# SCH_PET_tlacitko_V1_2023-06-28.net
KiCad netlist of a schematic drawn in EasyEDA
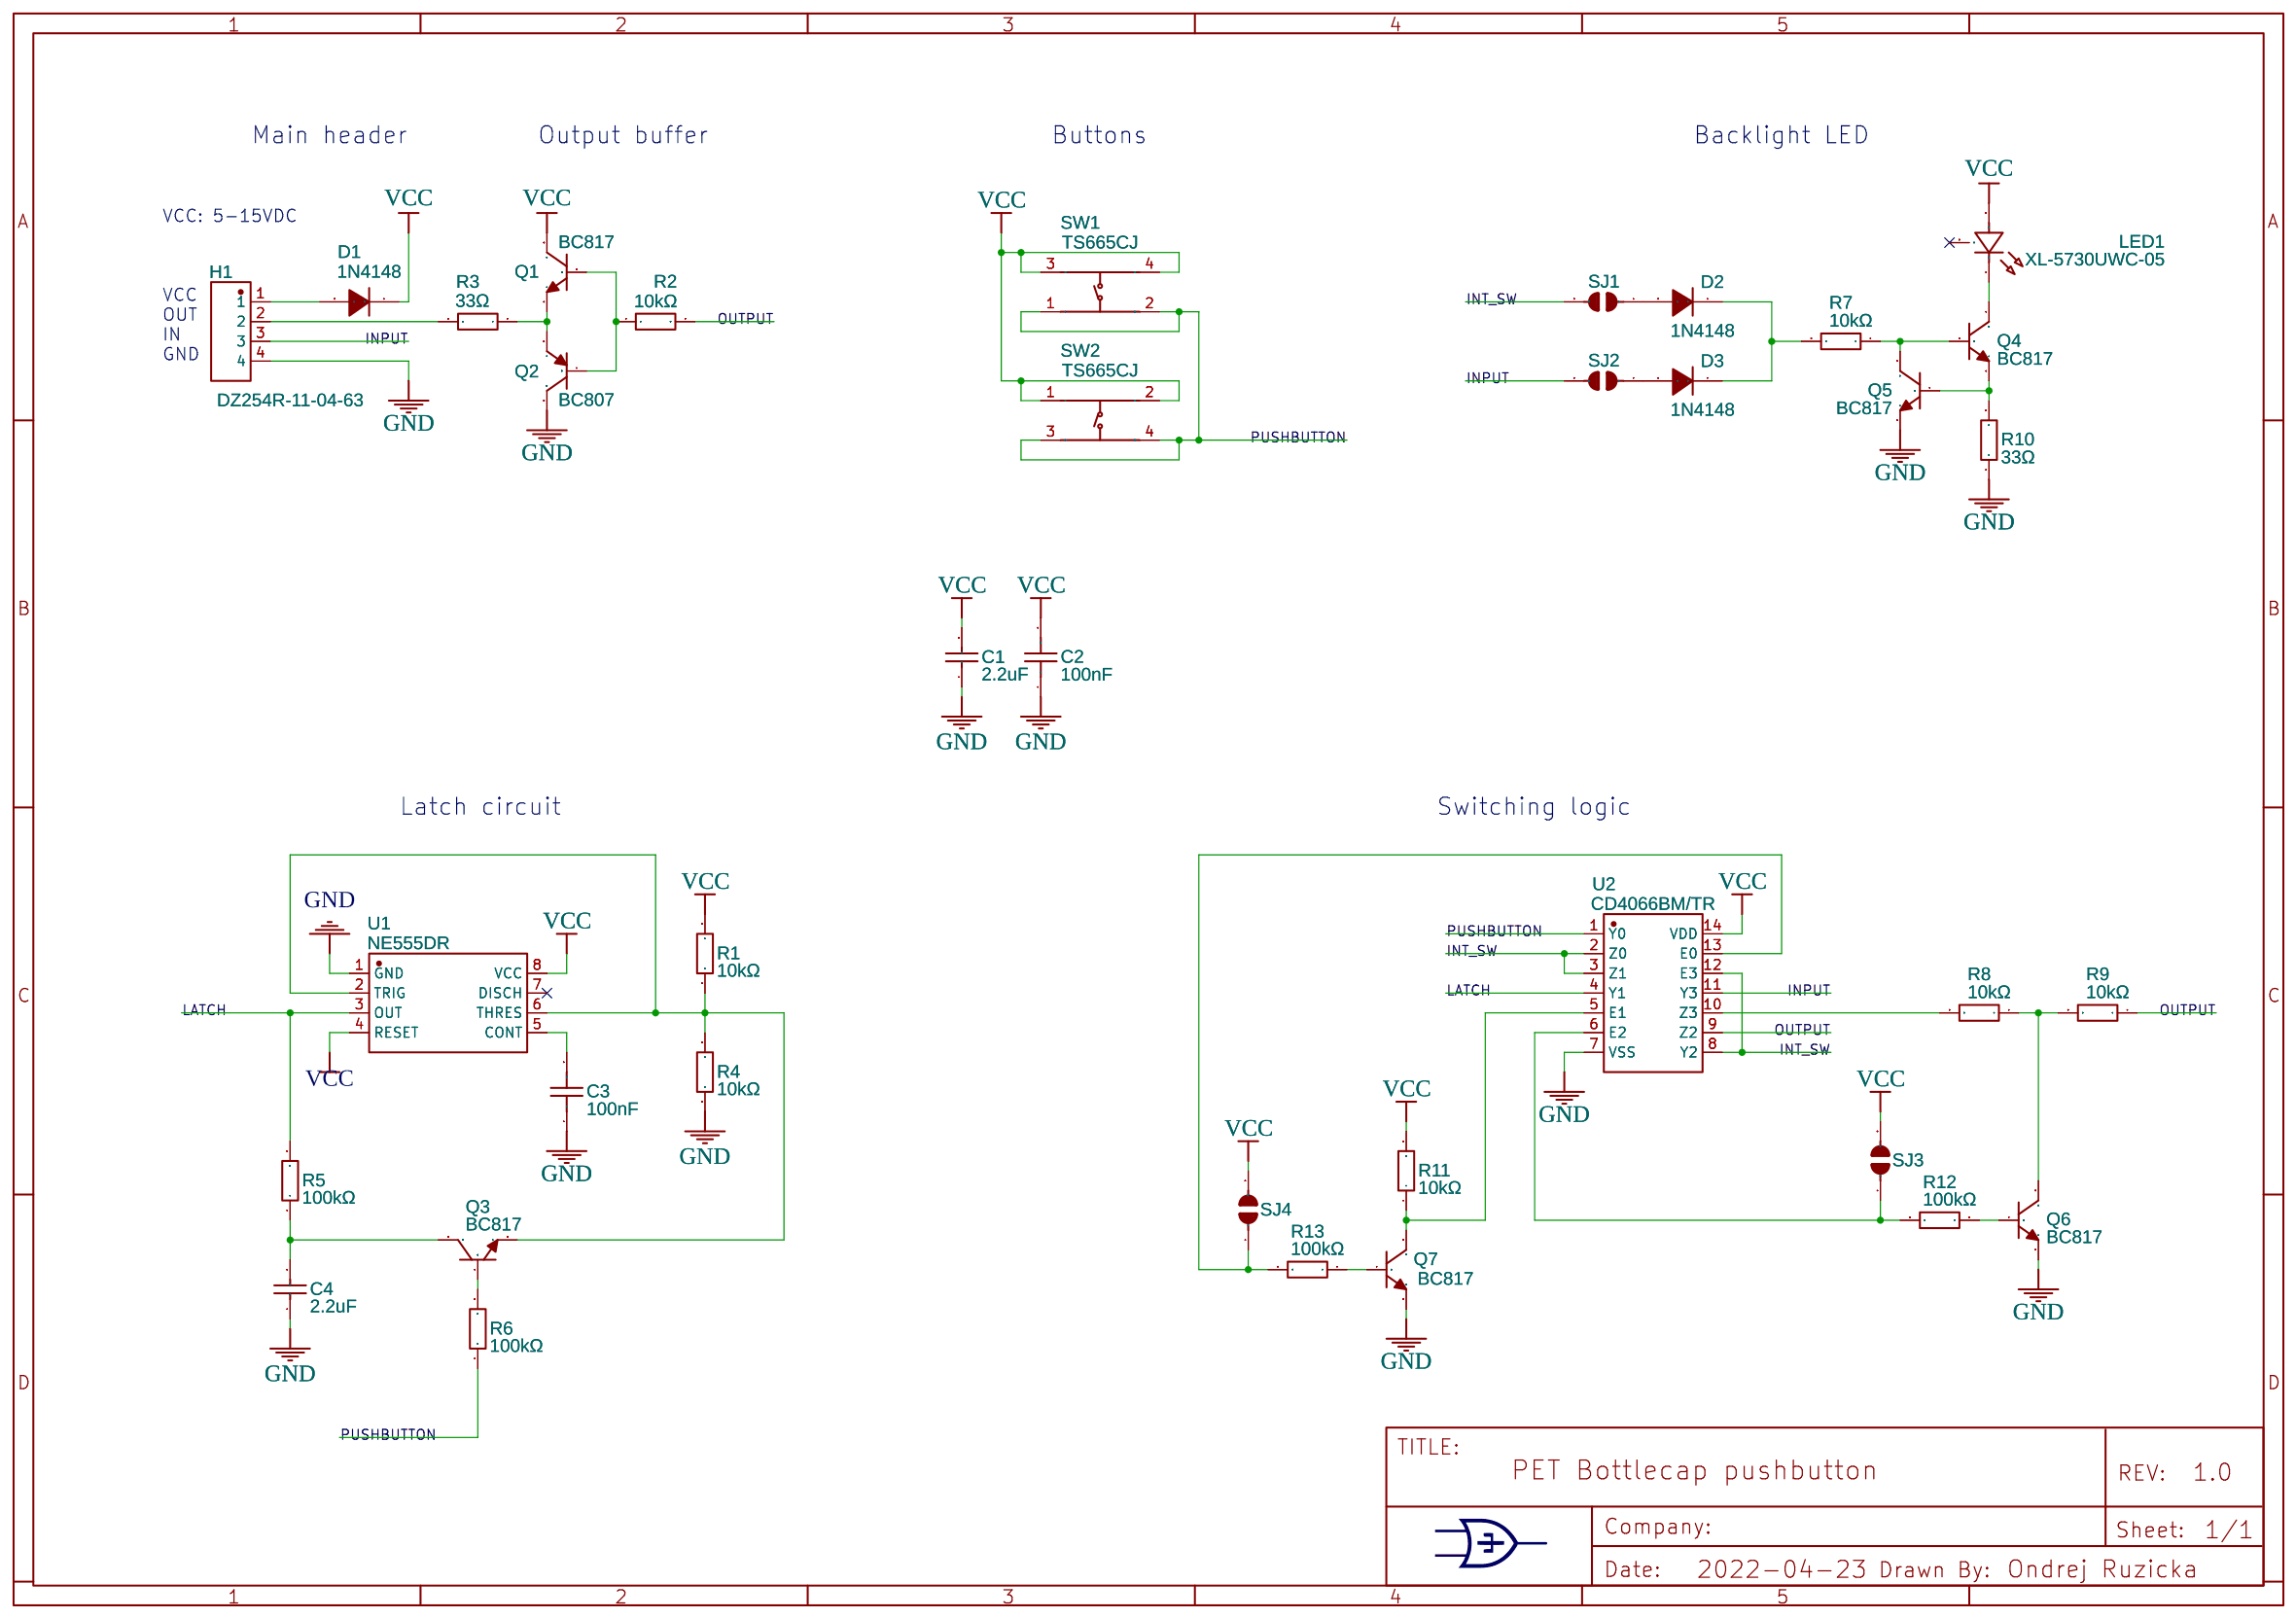
[diagram p0: schematic sheet]

(export (version "E")
  (design (tool "Eeschema 10.0.6"))
  (components
    (comp (ref "C1")
      (value "2.2uF")
      (fields
        (field (name "BOM_Manufacturer Part") "CL10A225KO8NNNC")
        (field (name "BOM_Supplier Part") "C23630")
      )
      (libsource (lib "") (part "CL10A225KO8NNNC"))
    )
    (comp (ref "C2")
      (value "100nF")
      (fields
        (field (name "BOM_Manufacturer Part") "CC0603KRX7R9BB104")
        (field (name "BOM_Supplier Part") "C14663")
      )
      (libsource (lib "") (part "CC0603KRX7R9BB104"))
    )
    (comp (ref "C3")
      (value "100nF")
      (fields
        (field (name "BOM_Manufacturer Part") "CC0603KRX7R9BB104")
        (field (name "BOM_Supplier Part") "C14663")
      )
      (libsource (lib "") (part "CC0603KRX7R9BB104"))
    )
    (comp (ref "C4")
      (value "2.2uF")
      (fields
        (field (name "BOM_Manufacturer Part") "CL10A225KO8NNNC")
        (field (name "BOM_Supplier Part") "C23630")
      )
      (libsource (lib "") (part "CL10A225KO8NNNC"))
    )
    (comp (ref "D1")
      (value "1N4148")
      (fields (field (name "BOM_Manufacturer Part") "1N4148W") (field (name "BOM_Supplier Part") "C115103"))
      (libsource (lib "") (part "1N4148W_C115103"))
    )
    (comp (ref "D2")
      (value "1N4148")
      (fields (field (name "BOM_Manufacturer Part") "1N4148W") (field (name "BOM_Supplier Part") "C115103"))
      (libsource (lib "") (part "1N4148W_C115103"))
    )
    (comp (ref "D3")
      (value "1N4148")
      (fields (field (name "BOM_Manufacturer Part") "1N4148W") (field (name "BOM_Supplier Part") "C115103"))
      (libsource (lib "") (part "1N4148W_C115103"))
    )
    (comp (ref "H1")
      (value "DZ254R-11-04-63")
      (fields (field (name "BOM_Supplier Part") "C2935910"))
      (libsource (lib "") (part "DZ254R-11-04-63"))
    )
    (comp (ref "LED1")
      (value "XL-5730UWC-05")
      (fields (field (name "BOM_Supplier Part") "C2843887"))
      (libsource (lib "") (part "XL-5730UWC-05"))
    )
    (comp (ref "Q1")
      (value "BC817")
      (fields (field (name "BOM_Supplier Part") "C475629"))
      (libsource (lib "") (part "BC817_C475629"))
    )
    (comp (ref "Q2")
      (value "BC807")
      (fields (field (name "BOM_Manufacturer Part") "BC807-25") (field (name "BOM_Supplier Part") "C556162"))
      (libsource (lib "") (part "BC807-25_C556162"))
    )
    (comp (ref "Q3")
      (value "BC817")
      (fields (field (name "BOM_Supplier Part") "C475629"))
      (libsource (lib "") (part "BC817_C475629_2"))
    )
    (comp (ref "Q4")
      (value "BC817")
      (fields (field (name "BOM_Supplier Part") "C475629"))
      (libsource (lib "") (part "BC817_C475629_1"))
    )
    (comp (ref "Q5")
      (value "BC817")
      (fields (field (name "BOM_Supplier Part") "C475629"))
      (libsource (lib "") (part "BC817_C475629"))
    )
    (comp (ref "Q6")
      (value "BC817")
      (fields (field (name "BOM_Supplier Part") "C475629"))
      (libsource (lib "") (part "BC817_C475629_1"))
    )
    (comp (ref "Q7")
      (value "BC817")
      (fields (field (name "BOM_Supplier Part") "C475629"))
      (libsource (lib "") (part "BC817_C475629_1"))
    )
    (comp (ref "R1")
      (value "10kΩ")
      (fields
        (field (name "BOM_Manufacturer Part") "0603WAF1002T5E")
        (field (name "BOM_Supplier Part") "C25804")
      )
      (libsource (lib "") (part "0603WAF1002T5E_1"))
    )
    (comp (ref "R2")
      (value "10kΩ")
      (fields
        (field (name "BOM_Manufacturer Part") "0603WAF1002T5E")
        (field (name "BOM_Supplier Part") "C25804")
      )
      (libsource (lib "") (part "0603WAF1002T5E_2"))
    )
    (comp (ref "R3")
      (value "33Ω")
      (fields
        (field (name "BOM_Manufacturer Part") "0603WAF330JT5E")
        (field (name "BOM_Supplier Part") "C23140")
      )
      (libsource (lib "") (part "0603WAF330JT5E"))
    )
    (comp (ref "R4")
      (value "10kΩ")
      (fields
        (field (name "BOM_Manufacturer Part") "0603WAF1002T5E")
        (field (name "BOM_Supplier Part") "C25804")
      )
      (libsource (lib "") (part "0603WAF1002T5E_1"))
    )
    (comp (ref "R5")
      (value "100kΩ")
      (fields
        (field (name "BOM_Manufacturer Part") "0603WAF1003T5E")
        (field (name "BOM_Supplier Part") "C25803")
      )
      (libsource (lib "") (part "0603WAF1003T5E"))
    )
    (comp (ref "R6")
      (value "100kΩ")
      (fields
        (field (name "BOM_Manufacturer Part") "0603WAF1003T5E")
        (field (name "BOM_Supplier Part") "C25803")
      )
      (libsource (lib "") (part "0603WAF1003T5E"))
    )
    (comp (ref "R7")
      (value "10kΩ")
      (fields
        (field (name "BOM_Manufacturer Part") "0603WAF1002T5E")
        (field (name "BOM_Supplier Part") "C25804")
      )
      (libsource (lib "") (part "0603WAF1002T5E"))
    )
    (comp (ref "R8")
      (value "10kΩ")
      (fields
        (field (name "BOM_Manufacturer Part") "0603WAF1002T5E")
        (field (name "BOM_Supplier Part") "C25804")
      )
      (libsource (lib "") (part "0603WAF1002T5E"))
    )
    (comp (ref "R9")
      (value "10kΩ")
      (fields
        (field (name "BOM_Manufacturer Part") "0603WAF1002T5E")
        (field (name "BOM_Supplier Part") "C25804")
      )
      (libsource (lib "") (part "0603WAF1002T5E"))
    )
    (comp (ref "R10")
      (value "33Ω")
      (fields
        (field (name "BOM_Manufacturer Part") "0603WAF330JT5E")
        (field (name "BOM_Supplier Part") "C23140")
      )
      (libsource (lib "") (part "0603WAF330JT5E_1"))
    )
    (comp (ref "R11")
      (value "10kΩ")
      (fields
        (field (name "BOM_Manufacturer Part") "0603WAF1002T5E")
        (field (name "BOM_Supplier Part") "C25804")
      )
      (libsource (lib "") (part "0603WAF1002T5E_1"))
    )
    (comp (ref "R12")
      (value "100kΩ")
      (fields
        (field (name "BOM_Manufacturer Part") "0603WAF1003T5E")
        (field (name "BOM_Supplier Part") "C25803")
      )
      (libsource (lib "") (part "0603WAF1003T5E_1"))
    )
    (comp (ref "R13")
      (value "100kΩ")
      (fields
        (field (name "BOM_Manufacturer Part") "0603WAF1003T5E")
        (field (name "BOM_Supplier Part") "C25803")
      )
      (libsource (lib "") (part "0603WAF1003T5E_1"))
    )
    (comp (ref "SJ1") (value "SOLDERJUMPERNO") (libsource (lib "") (part "SOLDERJUMPERNO")))
    (comp (ref "SJ2") (value "SOLDERJUMPERNO") (libsource (lib "") (part "SOLDERJUMPERNO")))
    (comp (ref "SJ3") (value "SOLDERJUMPERNO") (libsource (lib "") (part "SOLDERJUMPERNO_1")))
    (comp (ref "SJ4") (value "SOLDERJUMPERNO") (libsource (lib "") (part "SOLDERJUMPERNO_1")))
    (comp (ref "SW1")
      (value "TS665CJ")
      (fields (field (name "BOM_Supplier Part") "C393938"))
      (libsource (lib "") (part "TS665CJ_1"))
    )
    (comp (ref "SW2")
      (value "TS665CJ")
      (fields (field (name "BOM_Supplier Part") "C393938"))
      (libsource (lib "") (part "TS665CJ"))
    )
    (comp (ref "U1")
      (value "NE555DR")
      (fields (field (name "BOM_Supplier Part") "C695838"))
      (libsource (lib "") (part "NE555DR_C695838"))
    )
    (comp (ref "U2")
      (value "CD4066BM/TR")
      (fields (field (name "BOM_Supplier Part") "C512770"))
      (libsource (lib "") (part "CD4066BM/TR"))
    )
  )
  (nets
    (net (code "1") (name "/INPUT") (class "Default")
      (node (ref "H1") (pin "3") (pinfunction "3_3") (pintype "unspecified"))
      (node (ref "SJ2") (pin "2") (pinfunction "2_2") (pintype "unspecified"))
      (node (ref "U2") (pin "11") (pinfunction "Y3_11") (pintype "unspecified"))
    )
    (net (code "2") (name "/INT_SW") (class "Default")
      (node (ref "SJ1") (pin "2") (pinfunction "2_2") (pintype "unspecified"))
      (node (ref "U2") (pin "12") (pinfunction "E3_12") (pintype "unspecified"))
      (node (ref "U2") (pin "2") (pinfunction "Z0_2") (pintype "unspecified"))
      (node (ref "U2") (pin "3") (pinfunction "Z1_3") (pintype "unspecified"))
      (node (ref "U2") (pin "8") (pinfunction "Y2_8") (pintype "unspecified"))
    )
    (net (code "3") (name "/LATCH") (class "Default")
      (node (ref "R5") (pin "2") (pinfunction "2_2") (pintype "input"))
      (node (ref "U1") (pin "3") (pinfunction "OUT_3") (pintype "unspecified"))
      (node (ref "U2") (pin "4") (pinfunction "Y1_4") (pintype "unspecified"))
    )
    (net (code "4") (name "/OUTPUT") (class "Default")
      (node (ref "R2") (pin "2") (pinfunction "2_2") (pintype "input"))
      (node (ref "R9") (pin "1") (pinfunction "1_1") (pintype "input"))
      (node (ref "U2") (pin "9") (pinfunction "Z2_9") (pintype "unspecified"))
    )
    (net (code "5") (name "/PUSHBUTTON") (class "Default")
      (node (ref "R6") (pin "1") (pinfunction "1_1") (pintype "input"))
      (node (ref "SW1") (pin "1") (pinfunction "A_1") (pintype "unspecified"))
      (node (ref "SW1") (pin "2") (pinfunction "B_2") (pintype "unspecified"))
      (node (ref "SW2") (pin "3") (pinfunction "C_3") (pintype "unspecified"))
      (node (ref "SW2") (pin "4") (pinfunction "D_4") (pintype "unspecified"))
      (node (ref "U2") (pin "1") (pinfunction "Y0_1") (pintype "unspecified"))
    )
    (net (code "6") (name "GND") (class "Default")
      (node (ref "C1") (pin "1") (pinfunction "1_1") (pintype "input"))
      (node (ref "C2") (pin "1") (pinfunction "1_1") (pintype "unspecified"))
      (node (ref "C3") (pin "1") (pinfunction "1_1") (pintype "unspecified"))
      (node (ref "C4") (pin "1") (pinfunction "1_1") (pintype "input"))
      (node (ref "H1") (pin "4") (pinfunction "4_4") (pintype "unspecified"))
      (node (ref "Q2") (pin "3") (pinfunction "C_3") (pintype "unspecified"))
      (node (ref "Q5") (pin "2") (pinfunction "E_2") (pintype "unspecified"))
      (node (ref "Q6") (pin "2") (pinfunction "E_2") (pintype "unspecified"))
      (node (ref "Q7") (pin "2") (pinfunction "E_2") (pintype "unspecified"))
      (node (ref "R10") (pin "1") (pinfunction "1_1") (pintype "input"))
      (node (ref "R4") (pin "1") (pinfunction "1_1") (pintype "input"))
      (node (ref "U1") (pin "1") (pinfunction "GND_1") (pintype "unspecified"))
      (node (ref "U2") (pin "7") (pinfunction "VSS_7") (pintype "unspecified"))
    )
    (net (code "7") (name "Net-(D1-A)") (class "Default")
      (node (ref "D1") (pin "2") (pinfunction "A_2") (pintype "unspecified"))
      (node (ref "H1") (pin "1") (pinfunction "1_1") (pintype "unspecified"))
    )
    (net (code "8") (name "Net-(D2-A)") (class "Default")
      (node (ref "D2") (pin "2") (pinfunction "A_2") (pintype "unspecified"))
      (node (ref "SJ1") (pin "1") (pinfunction "1_1") (pintype "unspecified"))
    )
    (net (code "9") (name "Net-(D2-K)") (class "Default")
      (node (ref "D2") (pin "1") (pinfunction "K_1") (pintype "unspecified"))
      (node (ref "D3") (pin "1") (pinfunction "K_1") (pintype "unspecified"))
      (node (ref "R7") (pin "2") (pinfunction "2_2") (pintype "input"))
    )
    (net (code "10") (name "Net-(D3-A)") (class "Default")
      (node (ref "D3") (pin "2") (pinfunction "A_2") (pintype "unspecified"))
      (node (ref "SJ2") (pin "1") (pinfunction "1_1") (pintype "unspecified"))
    )
    (net (code "11") (name "Net-(H1-Pad2)") (class "Default")
      (node (ref "H1") (pin "2") (pinfunction "2_2") (pintype "unspecified"))
      (node (ref "R3") (pin "2") (pinfunction "2_2") (pintype "input"))
    )
    (net (code "12") (name "Net-(LED1-K)") (class "Default")
      (node (ref "LED1") (pin "1") (pinfunction "K_1") (pintype "unspecified"))
      (node (ref "Q4") (pin "3") (pinfunction "C_3") (pintype "unspecified"))
    )
    (net (code "13") (name "Net-(Q1-B)") (class "Default")
      (node (ref "Q1") (pin "1") (pinfunction "B_1") (pintype "unspecified"))
      (node (ref "Q2") (pin "1") (pinfunction "B_1") (pintype "unspecified"))
      (node (ref "R2") (pin "1") (pinfunction "1_1") (pintype "input"))
    )
    (net (code "14") (name "Net-(Q1-E)") (class "Default")
      (node (ref "Q1") (pin "2") (pinfunction "E_2") (pintype "unspecified"))
      (node (ref "Q2") (pin "2") (pinfunction "E_2") (pintype "unspecified"))
      (node (ref "R3") (pin "1") (pinfunction "1_1") (pintype "input"))
    )
    (net (code "15") (name "Net-(Q3-B)") (class "Default")
      (node (ref "Q3") (pin "1") (pinfunction "B_1") (pintype "unspecified"))
      (node (ref "R6") (pin "2") (pinfunction "2_2") (pintype "input"))
    )
    (net (code "16") (name "Net-(Q3-C)") (class "Default")
      (node (ref "C4") (pin "2") (pinfunction "2_2") (pintype "input"))
      (node (ref "Q3") (pin "3") (pinfunction "C_3") (pintype "unspecified"))
      (node (ref "R5") (pin "1") (pinfunction "1_1") (pintype "input"))
    )
    (net (code "17") (name "Net-(Q3-E)") (class "Default")
      (node (ref "Q3") (pin "2") (pinfunction "E_2") (pintype "unspecified"))
      (node (ref "R1") (pin "1") (pinfunction "1_1") (pintype "input"))
      (node (ref "R4") (pin "2") (pinfunction "2_2") (pintype "input"))
      (node (ref "U1") (pin "2") (pinfunction "TRIG_2") (pintype "unspecified"))
      (node (ref "U1") (pin "6") (pinfunction "THRES_6") (pintype "unspecified"))
    )
    (net (code "18") (name "Net-(Q4-B)") (class "Default")
      (node (ref "Q4") (pin "1") (pinfunction "B_1") (pintype "unspecified"))
      (node (ref "Q5") (pin "3") (pinfunction "C_3") (pintype "unspecified"))
      (node (ref "R7") (pin "1") (pinfunction "1_1") (pintype "input"))
    )
    (net (code "19") (name "Net-(Q4-E)") (class "Default")
      (node (ref "Q4") (pin "2") (pinfunction "E_2") (pintype "unspecified"))
      (node (ref "Q5") (pin "1") (pinfunction "B_1") (pintype "unspecified"))
      (node (ref "R10") (pin "2") (pinfunction "2_2") (pintype "input"))
    )
    (net (code "20") (name "Net-(Q6-B)") (class "Default")
      (node (ref "Q6") (pin "1") (pinfunction "B_1") (pintype "unspecified"))
      (node (ref "R12") (pin "1") (pinfunction "1_1") (pintype "input"))
    )
    (net (code "21") (name "Net-(Q6-C)") (class "Default")
      (node (ref "Q6") (pin "3") (pinfunction "C_3") (pintype "unspecified"))
      (node (ref "R8") (pin "1") (pinfunction "1_1") (pintype "input"))
      (node (ref "R9") (pin "2") (pinfunction "2_2") (pintype "input"))
    )
    (net (code "22") (name "Net-(Q7-B)") (class "Default")
      (node (ref "Q7") (pin "1") (pinfunction "B_1") (pintype "unspecified"))
      (node (ref "R13") (pin "1") (pinfunction "1_1") (pintype "input"))
    )
    (net (code "23") (name "Net-(Q7-C)") (class "Default")
      (node (ref "Q7") (pin "3") (pinfunction "C_3") (pintype "unspecified"))
      (node (ref "R11") (pin "1") (pinfunction "1_1") (pintype "input"))
      (node (ref "U2") (pin "5") (pinfunction "E1_5") (pintype "unspecified"))
    )
    (net (code "24") (name "Net-(U1-CONT)") (class "Default")
      (node (ref "C3") (pin "2") (pinfunction "2_2") (pintype "unspecified"))
      (node (ref "U1") (pin "5") (pinfunction "CONT_5") (pintype "unspecified"))
    )
    (net (code "25") (name "Net-(U2-E0)") (class "Default")
      (node (ref "R13") (pin "2") (pinfunction "2_2") (pintype "input"))
      (node (ref "SJ4") (pin "1") (pinfunction "1_1") (pintype "unspecified"))
      (node (ref "U2") (pin "13") (pinfunction "E0_13") (pintype "unspecified"))
    )
    (net (code "26") (name "Net-(U2-E2)") (class "Default")
      (node (ref "R12") (pin "2") (pinfunction "2_2") (pintype "input"))
      (node (ref "SJ3") (pin "1") (pinfunction "1_1") (pintype "unspecified"))
      (node (ref "U2") (pin "6") (pinfunction "E2_6") (pintype "unspecified"))
    )
    (net (code "27") (name "Net-(U2-Z3)") (class "Default")
      (node (ref "R8") (pin "2") (pinfunction "2_2") (pintype "input"))
      (node (ref "U2") (pin "10") (pinfunction "Z3_10") (pintype "unspecified"))
    )
    (net (code "28") (name "VCC") (class "Default")
      (node (ref "C1") (pin "2") (pinfunction "2_2") (pintype "input"))
      (node (ref "C2") (pin "2") (pinfunction "2_2") (pintype "unspecified"))
      (node (ref "D1") (pin "1") (pinfunction "K_1") (pintype "unspecified"))
      (node (ref "LED1") (pin "2") (pinfunction "A_2") (pintype "unspecified"))
      (node (ref "Q1") (pin "3") (pinfunction "C_3") (pintype "unspecified"))
      (node (ref "R1") (pin "2") (pinfunction "2_2") (pintype "input"))
      (node (ref "R11") (pin "2") (pinfunction "2_2") (pintype "input"))
      (node (ref "SJ3") (pin "2") (pinfunction "2_2") (pintype "unspecified"))
      (node (ref "SJ4") (pin "2") (pinfunction "2_2") (pintype "unspecified"))
      (node (ref "SW1") (pin "3") (pinfunction "C_3") (pintype "unspecified"))
      (node (ref "SW1") (pin "4") (pinfunction "D_4") (pintype "unspecified"))
      (node (ref "SW2") (pin "1") (pinfunction "A_1") (pintype "unspecified"))
      (node (ref "SW2") (pin "2") (pinfunction "B_2") (pintype "unspecified"))
      (node (ref "U1") (pin "4") (pinfunction "RESET_4") (pintype "unspecified"))
      (node (ref "U1") (pin "8") (pinfunction "VCC_8") (pintype "unspecified"))
      (node (ref "U2") (pin "14") (pinfunction "VDD_14") (pintype "unspecified"))
    )
    (net (code "29") (name "unconnected-(LED1-Pad3)") (class "Default")
      (node (ref "LED1") (pin "3") (pinfunction "3_3") (pintype "unspecified+no_connect"))
    )
    (net (code "30") (name "unconnected-(U1-DISCH-Pad7)") (class "Default")
      (node (ref "U1") (pin "7") (pinfunction "DISCH_7") (pintype "unspecified+no_connect"))
    )
  )
)
